# JC_Linearity_Board.net
KiCad netlist of a schematic drawn in Altium Designer
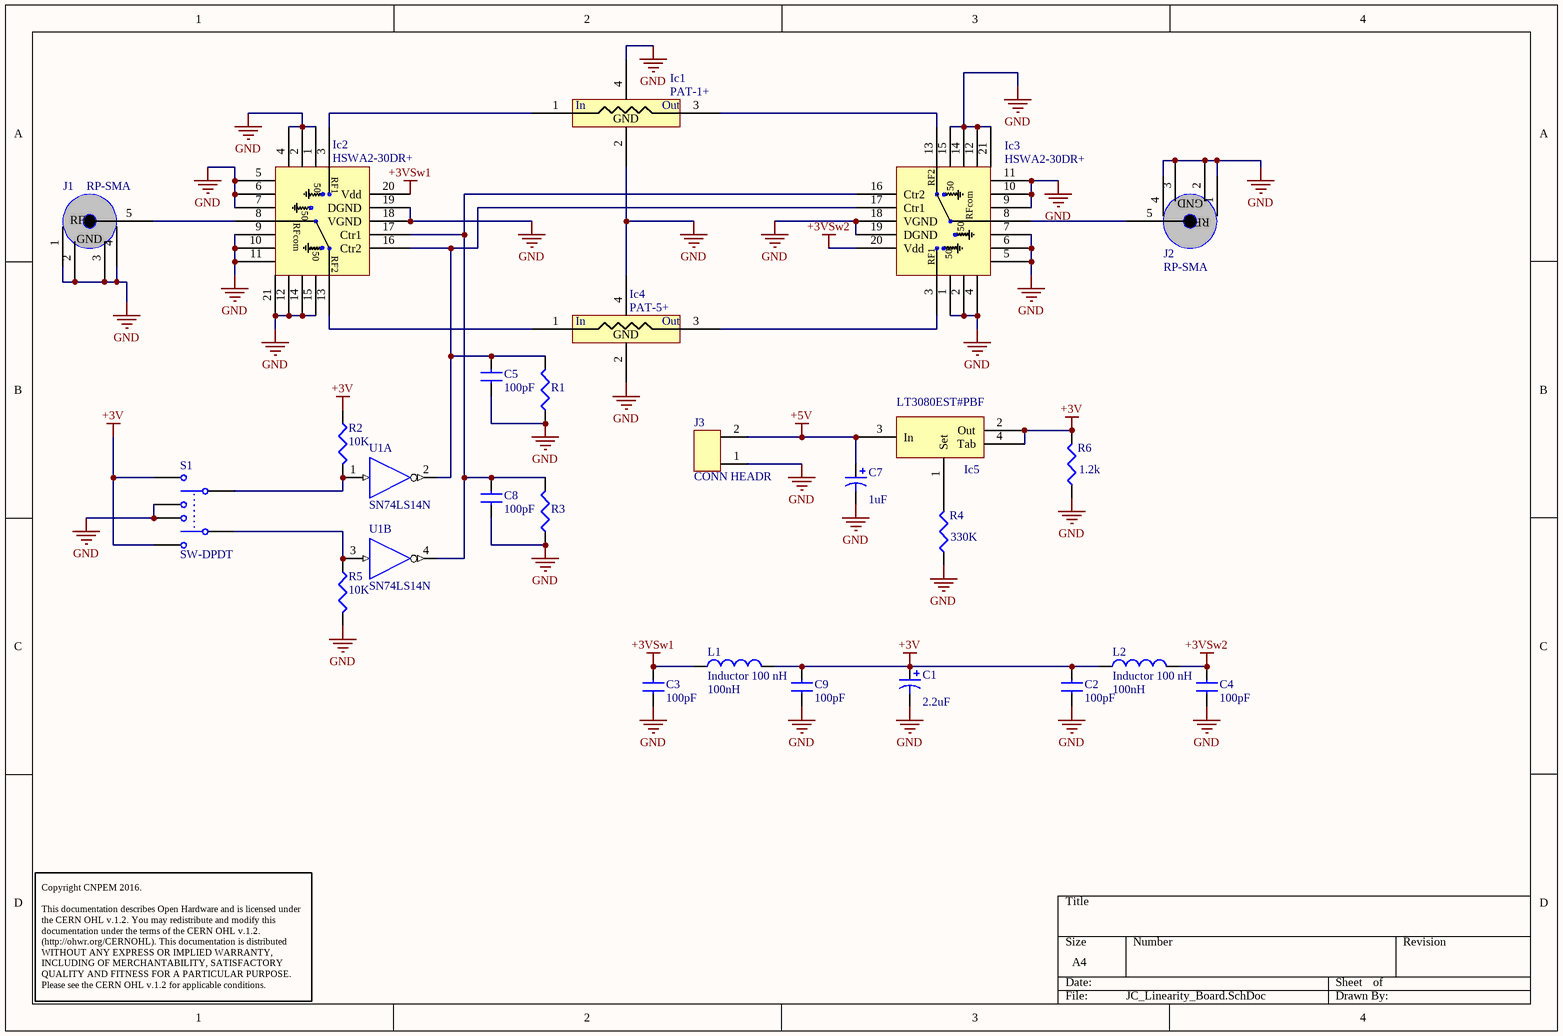
[diagram p0: JC_Linearity_Board.SchDoc]

(export (version "E")
  (design (tool "Eeschema 10.0.6"))
  (components
    (comp (ref "C1")
      (value "2.2uF")
      (footprint "CAPC3225M")
      (description "Polarized Capacitor (Surface Mount)")
      (fields (field (name "Comment") "C1608Y5V1C225Z") (field (name "PUBLISHER") "Altium Limited"))
      (libsource (lib "Miscellaneous Devices") (part "Cap Pol3"))
    )
    (comp (ref "C2")
      (value "C1608C0G1H101J")
      (footprint "CAPC1608N")
      (description "CAP CER 100PF 50V 5% NP0 0603")
      (fields
        (field (name "MANUFACTURER") "TDK Corporation")
        (field (name "TOLERANCE") "±5%")
        (field (name "CAPACITANCE") "100pF")
      )
      (libsource (lib "General DevicesRFFE") (part "C1608C0G1H101J"))
    )
    (comp (ref "C3")
      (value "C1608C0G1H101J")
      (footprint "CAPC1608N")
      (description "CAP CER 100PF 50V 5% NP0 0603")
      (fields
        (field (name "MANUFACTURER") "TDK Corporation")
        (field (name "TOLERANCE") "±5%")
        (field (name "CAPACITANCE") "100pF")
      )
      (libsource (lib "General DevicesRFFE") (part "C1608C0G1H101J"))
    )
    (comp (ref "C4")
      (value "C1608C0G1H101J")
      (footprint "CAPC1608N")
      (description "CAP CER 100PF 50V 5% NP0 0603")
      (fields
        (field (name "MANUFACTURER") "TDK Corporation")
        (field (name "TOLERANCE") "±5%")
        (field (name "CAPACITANCE") "100pF")
      )
      (libsource (lib "General DevicesRFFE") (part "C1608C0G1H101J"))
    )
    (comp (ref "C5")
      (value "C1608C0G1H101J")
      (footprint "CAPC1608N")
      (description "CAP CER 100PF 50V 5% NP0 0603")
      (fields
        (field (name "MANUFACTURER") "TDK Corporation")
        (field (name "TOLERANCE") "±5%")
        (field (name "CAPACITANCE") "100pF")
      )
      (libsource (lib "General DevicesRFFE") (part "C1608C0G1H101J"))
    )
    (comp (ref "C7")
      (value "1uF")
      (footprint "CAPC3225M")
      (description "'CAP CER 100PF 50V 5% NP0 0603")
      (fields (field (name "Comment") "C1608Y5V1C225Z") (field (name "PUBLISHER") "Altium Limited"))
      (libsource (lib "Miscellaneous Devices") (part "Cap Pol3"))
    )
    (comp (ref "C8")
      (value "C1608C0G1H101J")
      (footprint "CAPC1608N")
      (description "CAP CER 100PF 50V 5% NP0 0603")
      (fields
        (field (name "MANUFACTURER") "TDK Corporation")
        (field (name "TOLERANCE") "±5%")
        (field (name "CAPACITANCE") "100pF")
      )
      (libsource (lib "General DevicesRFFE") (part "C1608C0G1H101J"))
    )
    (comp (ref "C9")
      (value "C1608C0G1H101J")
      (footprint "CAPC1608N")
      (description "CAP CER 100PF 50V 5% NP0 0603")
      (fields
        (field (name "MANUFACTURER") "TDK Corporation")
        (field (name "TOLERANCE") "±5%")
        (field (name "CAPACITANCE") "100pF")
      )
      (libsource (lib "General DevicesRFFE") (part "C1608C0G1H101J"))
    )
    (comp (ref "Ic1")
      (value "PAT-1+")
      (footprint "AF320")
      (description "Fixed Attenuator 1 dB")
      (fields (field (name "MANUFACTURER") "Minicircuits"))
      (libsource (lib "ComponentesRF") (part "Minicircuits-PAT-1+"))
    )
    (comp (ref "Ic2")
      (value "HSWA2-30DR+")
      (footprint "DG983-1")
      (description "Absoptive RF Switch SPDT")
      (fields (field (name "MANUFACTURER") "Minicircuits"))
      (libsource (lib "ComponentesRF") (part "Minicircuits-HSWA2-30DR+"))
    )
    (comp (ref "Ic3")
      (value "HSWA2-30DR+")
      (footprint "DG983-1")
      (description "Absoptive RF Switch SPDT")
      (fields (field (name "MANUFACTURER") "Minicircuits"))
      (libsource (lib "") (part "Minicircuits-HSWA2-30DR+_1"))
    )
    (comp (ref "Ic4")
      (value "PAT-5+")
      (footprint "AF320")
      (description "Fixed Attenuator 3 dB")
      (fields (field (name "MANUFACTURER") "Minicircuits") (field (name "MANUFACTURER PART NUMBER") "PAT-3+"))
      (libsource (lib "ComponentesRF") (part "Minicircuits-PAT-3+"))
    )
    (comp (ref "Ic5")
      (value "LT3080EST#PBF")
      (footprint "SOT223-4L")
      (description "IC REG LDO 1.1A ADJ SOT223-3")
      (fields (field (name "MANUFACTURER") "Linear Technology"))
      (libsource (lib "General Devices") (part "LT3080EST#PBF"))
    )
    (comp (ref "J1")
      (value "CONN SMA")
      (footprint "SMAedge50R")
      (description "CONN RCPT BLKHD SMA REV POL PCB")
      (fields
        (field (name "MANUFACTURER") "Amphenol Connex")
        (field (name "MANUFACTURER PART NUMBER") "132289RP")
        (field (name "CONNECTOR STYLE") "RP-SMA")
      )
      (libsource (lib "ComponentesRF") (part "132289RP"))
    )
    (comp (ref "J2")
      (value "CONN SMA")
      (footprint "SMAedge50R")
      (description "CONN RCPT BLKHD SMA REV POL PCB")
      (fields
        (field (name "MANUFACTURER") "Amphenol Connex")
        (field (name "MANUFACTURER PART NUMBER") "132289RP")
        (field (name "CONNECTOR STYLE") "RP-SMA")
      )
      (libsource (lib "ComponentesRF") (part "132289RP"))
    )
    (comp (ref "J3")
      (value "CONN HEADR")
      (footprint "HDR1X2H")
      (description "CONN HEADR BRKWAY .100 2POS STR")
      (fields
        (field (name "MANUFACTURER") "TE Connectivity")
        (field (name "MANUFACTURER PART NUMBER") "4-103321-4")
      )
      (libsource (lib "General DevicesRFFE") (part "4-103321-4"))
    )
    (comp (ref "L1")
      (value "Inductor 100 nH")
      (footprint "CAPC1608M")
      (fields (field (name "ALTIUM_VALUE") "100nH") (field (name "PUBLISHER") "Altium Limited"))
      (libsource (lib "Miscellaneous Devices") (part "Inductor"))
    )
    (comp (ref "L2")
      (value "Inductor 100 nH")
      (footprint "CAPC1608M")
      (fields (field (name "ALTIUM_VALUE") "100nH") (field (name "PUBLISHER") "Altium Limited"))
      (libsource (lib "Miscellaneous Devices") (part "Inductor"))
    )
    (comp (ref "R1")
      (value "ERJ-3GEYJ103V")
      (footprint "RESC2012M")
      (description "RES 10K OHM 1/10W 5% 0603 SMD")
      (fields (field (name "MANUFACTURER") "Panasonic - ECG") (field (name "TOLERANCE") "±5%"))
      (libsource (lib "General DevicesRFFE") (part "ERJ-3GEYJ103V"))
    )
    (comp (ref "R2")
      (value "PNM0603E1002BST5")
      (footprint "RESC2012M")
      (description "RES 10K OHM .15W 0.1% 0603 SMD")
      (fields
        (field (name "MANUFACTURER") "Vishay Thin Film")
        (field (name "TOLERANCE") "±0.1%")
        (field (name "RESISTANCE (OHMS)") "10K")
      )
      (libsource (lib "General DevicesRFFE") (part "PNM0603E1002BST5"))
    )
    (comp (ref "R3")
      (value "ERJ-3GEYJ103V")
      (footprint "RESC2012M")
      (description "RES 10K OHM 1/10W 5% 0603 SMD")
      (fields (field (name "MANUFACTURER") "Panasonic - ECG") (field (name "TOLERANCE") "±5%"))
      (libsource (lib "General DevicesRFFE") (part "ERJ-3GEYJ103V"))
    )
    (comp (ref "R4")
      (value "330K")
      (footprint "RESC2012M")
      (description "RES 330K OHM 1/10W 5% 0603 SMD")
      (fields (field (name "Comment") "ERJ-3GEYJ334V") (field (name "PUBLISHER") "Altium Limited"))
      (libsource (lib "Miscellaneous Devices") (part "Res3"))
    )
    (comp (ref "R5")
      (value "PNM0603E1002BST5")
      (footprint "RESC2012M")
      (description "RES 10K OHM .15W 0.1% 0603 SMD")
      (fields
        (field (name "MANUFACTURER") "Vishay Thin Film")
        (field (name "TOLERANCE") "±0.1%")
        (field (name "RESISTANCE (OHMS)") "10K")
      )
      (libsource (lib "General DevicesRFFE") (part "PNM0603E1002BST5"))
    )
    (comp (ref "R6")
      (value "1.2k")
      (footprint "RESC2012M")
      (description "RES 1K2 OHM 1/10W 5% 0603 SMD")
      (fields (field (name "Comment") "ERJ-3GEYJ122V") (field (name "PUBLISHER") "Altium Limited"))
      (libsource (lib "Miscellaneous Devices") (part "Res3"))
    )
    (comp (ref "S1")
      (value "SW-DPDT")
      (footprint "DPDT-6")
      (description "Double-Pole, Double-Throw Switch")
      (fields (field (name "PUBLISHER") "Altium Limited"))
      (libsource (lib "Miscellaneous Devices") (part "SW-DPDT"))
    )
    (comp (ref "U1")
      (value "SN74LS14N")
      (footprint "646-06")
      (description "Hex Schmitt-Trigger Inverter")
      (fields (field (name "PUBLISHER") "Altium Limited"))
      (libsource (lib "ON Semi Logic Buffer Line Driver") (part "SN74LS14N"))
    )
  )
  (nets
    (net (code "1") (name "+3V") (class "Default")
      (node (ref "C1") (pin "1") (pinfunction "1_1") (pintype "passive"))
      (node (ref "C2") (pin "1") (pinfunction "1_1") (pintype "passive"))
      (node (ref "C9") (pin "1") (pinfunction "1_1") (pintype "passive"))
      (node (ref "Ic5") (pin "2") (pinfunction "Out_2") (pintype "passive"))
      (node (ref "Ic5") (pin "4") (pinfunction "Tab_4") (pintype "passive"))
      (node (ref "L1") (pin "2") (pinfunction "2_2") (pintype "passive"))
      (node (ref "L2") (pin "1") (pinfunction "1_1") (pintype "passive"))
      (node (ref "R2") (pin "2") (pinfunction "2_2") (pintype "passive"))
      (node (ref "R6") (pin "2") (pinfunction "2_2") (pintype "passive"))
      (node (ref "S1") (pin "2") (pinfunction "2_2") (pintype "passive"))
      (node (ref "S1") (pin "6") (pinfunction "6_6") (pintype "passive"))
    )
    (net (code "2") (name "+3VSw1") (class "Default")
      (node (ref "C3") (pin "1") (pinfunction "1_1") (pintype "passive"))
      (node (ref "Ic2") (pin "20") (pinfunction "Vdd_20") (pintype "passive"))
      (node (ref "L1") (pin "1") (pinfunction "1_1") (pintype "passive"))
    )
    (net (code "3") (name "+3VSw2") (class "Default")
      (node (ref "C4") (pin "1") (pinfunction "1_1") (pintype "passive"))
      (node (ref "Ic3") (pin "20") (pinfunction "Vdd_20") (pintype "passive"))
      (node (ref "L2") (pin "2") (pinfunction "2_2") (pintype "passive"))
    )
    (net (code "4") (name "+5V") (class "Default")
      (node (ref "C7") (pin "1") (pinfunction "1_1") (pintype "passive"))
      (node (ref "Ic5") (pin "3") (pinfunction "In_3") (pintype "passive"))
      (node (ref "J3") (pin "2") (pinfunction "2_2") (pintype "passive"))
    )
    (net (code "5") (name "GND") (class "Default")
      (node (ref "C1") (pin "2") (pinfunction "2_2") (pintype "passive"))
      (node (ref "C2") (pin "2") (pinfunction "2_2") (pintype "passive"))
      (node (ref "C3") (pin "2") (pinfunction "2_2") (pintype "passive"))
      (node (ref "C4") (pin "2") (pinfunction "2_2") (pintype "passive"))
      (node (ref "C5") (pin "2") (pinfunction "2_2") (pintype "passive"))
      (node (ref "C7") (pin "2") (pinfunction "2_2") (pintype "passive"))
      (node (ref "C8") (pin "2") (pinfunction "2_2") (pintype "passive"))
      (node (ref "C9") (pin "2") (pinfunction "2_2") (pintype "passive"))
      (node (ref "Ic1") (pin "2") (pinfunction "GND_2") (pintype "passive"))
      (node (ref "Ic1") (pin "4") (pinfunction "GND_4") (pintype "passive"))
      (node (ref "Ic2") (pin "1") (pinfunction "GND_1") (pintype "passive"))
      (node (ref "Ic2") (pin "10") (pinfunction "GND_10") (pintype "passive"))
      (node (ref "Ic2") (pin "11") (pinfunction "GND_11") (pintype "passive"))
      (node (ref "Ic2") (pin "12") (pinfunction "GND_12") (pintype "passive"))
      (node (ref "Ic2") (pin "14") (pinfunction "GND_14") (pintype "passive"))
      (node (ref "Ic2") (pin "15") (pinfunction "GND_15") (pintype "passive"))
      (node (ref "Ic2") (pin "18") (pinfunction "VGND_18") (pintype "passive"))
      (node (ref "Ic2") (pin "19") (pinfunction "DGND_19") (pintype "passive"))
      (node (ref "Ic2") (pin "2") (pinfunction "GND_2") (pintype "passive"))
      (node (ref "Ic2") (pin "21") (pinfunction "GND_21") (pintype "passive"))
      (node (ref "Ic2") (pin "4") (pinfunction "GND_4") (pintype "passive"))
      (node (ref "Ic2") (pin "5") (pinfunction "GND_5") (pintype "passive"))
      (node (ref "Ic2") (pin "6") (pinfunction "GND_6") (pintype "passive"))
      (node (ref "Ic2") (pin "7") (pinfunction "GND_7") (pintype "passive"))
      (node (ref "Ic2") (pin "9") (pinfunction "GND_9") (pintype "passive"))
      (node (ref "Ic3") (pin "1") (pinfunction "GND_1") (pintype "passive"))
      (node (ref "Ic3") (pin "10") (pinfunction "GND_10") (pintype "passive"))
      (node (ref "Ic3") (pin "11") (pinfunction "GND_11") (pintype "passive"))
      (node (ref "Ic3") (pin "12") (pinfunction "GND_12") (pintype "passive"))
      (node (ref "Ic3") (pin "14") (pinfunction "GND_14") (pintype "passive"))
      (node (ref "Ic3") (pin "15") (pinfunction "GND_15") (pintype "passive"))
      (node (ref "Ic3") (pin "18") (pinfunction "VGND_18") (pintype "passive"))
      (node (ref "Ic3") (pin "19") (pinfunction "DGND_19") (pintype "passive"))
      (node (ref "Ic3") (pin "2") (pinfunction "GND_2") (pintype "passive"))
      (node (ref "Ic3") (pin "21") (pinfunction "GND_21") (pintype "passive"))
      (node (ref "Ic3") (pin "4") (pinfunction "GND_4") (pintype "passive"))
      (node (ref "Ic3") (pin "5") (pinfunction "GND_5") (pintype "passive"))
      (node (ref "Ic3") (pin "6") (pinfunction "GND_6") (pintype "passive"))
      (node (ref "Ic3") (pin "7") (pinfunction "GND_7") (pintype "passive"))
      (node (ref "Ic3") (pin "9") (pinfunction "GND_9") (pintype "passive"))
      (node (ref "Ic4") (pin "2") (pinfunction "GND_2") (pintype "passive"))
      (node (ref "Ic4") (pin "4") (pinfunction "GND_4") (pintype "passive"))
      (node (ref "J1") (pin "1") (pinfunction "GND_1") (pintype "passive"))
      (node (ref "J1") (pin "2") (pinfunction "GND_2") (pintype "passive"))
      (node (ref "J1") (pin "3") (pinfunction "GND_3") (pintype "passive"))
      (node (ref "J1") (pin "4") (pinfunction "GND_4") (pintype "passive"))
      (node (ref "J2") (pin "1") (pinfunction "GND_1") (pintype "passive"))
      (node (ref "J2") (pin "2") (pinfunction "GND_2") (pintype "passive"))
      (node (ref "J2") (pin "3") (pinfunction "GND_3") (pintype "passive"))
      (node (ref "J2") (pin "4") (pinfunction "GND_4") (pintype "passive"))
      (node (ref "J3") (pin "1") (pinfunction "1_1") (pintype "passive"))
      (node (ref "R1") (pin "2") (pinfunction "2_2") (pintype "passive"))
      (node (ref "R3") (pin "2") (pinfunction "2_2") (pintype "passive"))
      (node (ref "R4") (pin "1") (pinfunction "1_1") (pintype "passive"))
      (node (ref "R5") (pin "1") (pinfunction "1_1") (pintype "passive"))
      (node (ref "R6") (pin "1") (pinfunction "1_1") (pintype "passive"))
      (node (ref "S1") (pin "3") (pinfunction "3_3") (pintype "passive"))
      (node (ref "S1") (pin "5") (pinfunction "5_5") (pintype "passive"))
      (node (ref "U1") (pin "7") (pinfunction "GND_7") (pintype "power_in"))
    )
    (net (code "6") (name "Net-(Ic1-In)") (class "Default")
      (node (ref "Ic1") (pin "1") (pinfunction "In_1") (pintype "passive"))
      (node (ref "Ic2") (pin "3") (pinfunction "RF1_3") (pintype "passive"))
    )
    (net (code "7") (name "Net-(Ic1-Out)") (class "Default")
      (node (ref "Ic1") (pin "3") (pinfunction "Out_3") (pintype "passive"))
      (node (ref "Ic3") (pin "13") (pinfunction "RF2_13") (pintype "passive"))
    )
    (net (code "8") (name "Net-(Ic2-Ctr1)") (class "Default")
      (node (ref "C8") (pin "1") (pinfunction "1_1") (pintype "passive"))
      (node (ref "Ic2") (pin "17") (pinfunction "Ctr1_17") (pintype "passive"))
      (node (ref "Ic3") (pin "16") (pinfunction "Ctr2_16") (pintype "passive"))
      (node (ref "R3") (pin "1") (pinfunction "1_1") (pintype "passive"))
      (node (ref "U1") (pin "4") (pinfunction "~{OUT}_4") (pintype "output"))
    )
    (net (code "9") (name "Net-(Ic2-Ctr2)") (class "Default")
      (node (ref "C5") (pin "1") (pinfunction "1_1") (pintype "passive"))
      (node (ref "Ic2") (pin "16") (pinfunction "Ctr2_16") (pintype "passive"))
      (node (ref "Ic3") (pin "17") (pinfunction "Ctr1_17") (pintype "passive"))
      (node (ref "R1") (pin "1") (pinfunction "1_1") (pintype "passive"))
      (node (ref "U1") (pin "2") (pinfunction "~{OUT}_2") (pintype "output"))
    )
    (net (code "10") (name "Net-(Ic2-RF2)") (class "Default")
      (node (ref "Ic2") (pin "13") (pinfunction "RF2_13") (pintype "passive"))
      (node (ref "Ic4") (pin "1") (pinfunction "In_1") (pintype "passive"))
    )
    (net (code "11") (name "Net-(Ic2-RFcom)") (class "Default")
      (node (ref "Ic2") (pin "8") (pinfunction "RFcom_8") (pintype "passive"))
      (node (ref "J1") (pin "5") (pinfunction "RFin_5") (pintype "passive"))
    )
    (net (code "12") (name "Net-(Ic3-RF1)") (class "Default")
      (node (ref "Ic3") (pin "3") (pinfunction "RF1_3") (pintype "passive"))
      (node (ref "Ic4") (pin "3") (pinfunction "Out_3") (pintype "passive"))
    )
    (net (code "13") (name "Net-(Ic3-RFcom)") (class "Default")
      (node (ref "Ic3") (pin "8") (pinfunction "RFcom_8") (pintype "passive"))
      (node (ref "J2") (pin "5") (pinfunction "RFin_5") (pintype "passive"))
    )
    (net (code "14") (name "Net-(Ic5-Set)") (class "Default")
      (node (ref "Ic5") (pin "1") (pinfunction "Set_1") (pintype "passive"))
      (node (ref "R4") (pin "2") (pinfunction "2_2") (pintype "passive"))
    )
    (net (code "15") (name "Net-(U1A-IN)") (class "Default")
      (node (ref "R2") (pin "1") (pinfunction "1_1") (pintype "passive"))
      (node (ref "S1") (pin "4") (pinfunction "4_4") (pintype "passive"))
      (node (ref "U1") (pin "1") (pinfunction "IN_1") (pintype "input"))
    )
    (net (code "16") (name "Net-(U1B-IN)") (class "Default")
      (node (ref "R5") (pin "2") (pinfunction "2_2") (pintype "passive"))
      (node (ref "S1") (pin "1") (pinfunction "1_1") (pintype "passive"))
      (node (ref "U1") (pin "3") (pinfunction "IN_3") (pintype "input"))
    )
    (net (code "17") (name "VDD") (class "Default")
      (node (ref "U1") (pin "14") (pinfunction "VDD_14") (pintype "power_in"))
    )
  )
)
